# cos_POC.net
KiCad netlist of a schematic drawn in EAGLE
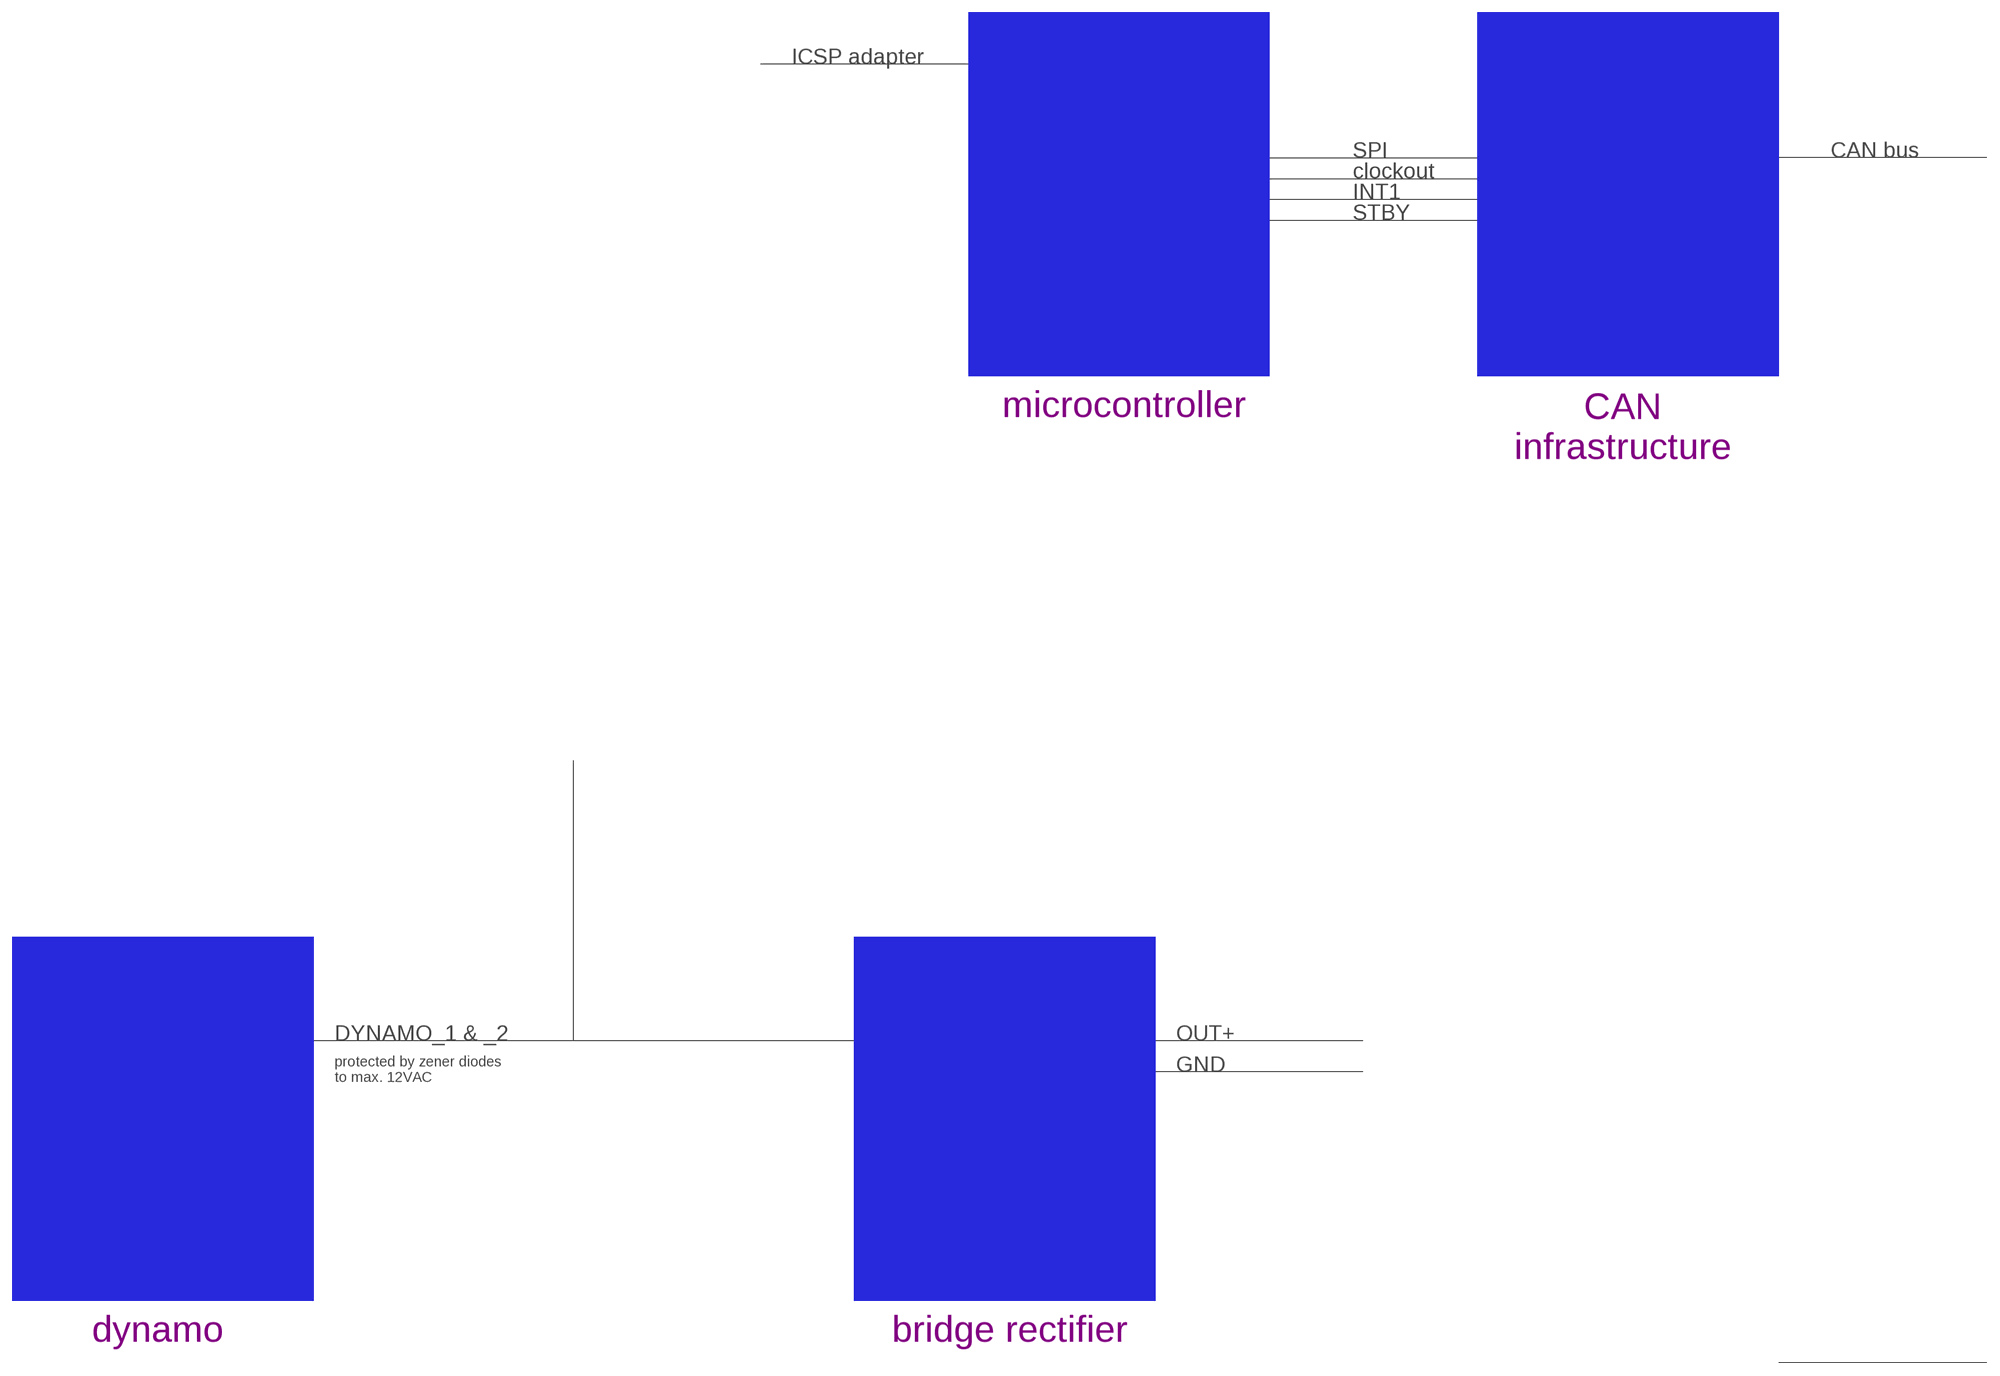
[diagram p0: schematic, sheet 1, part 1 of 3]
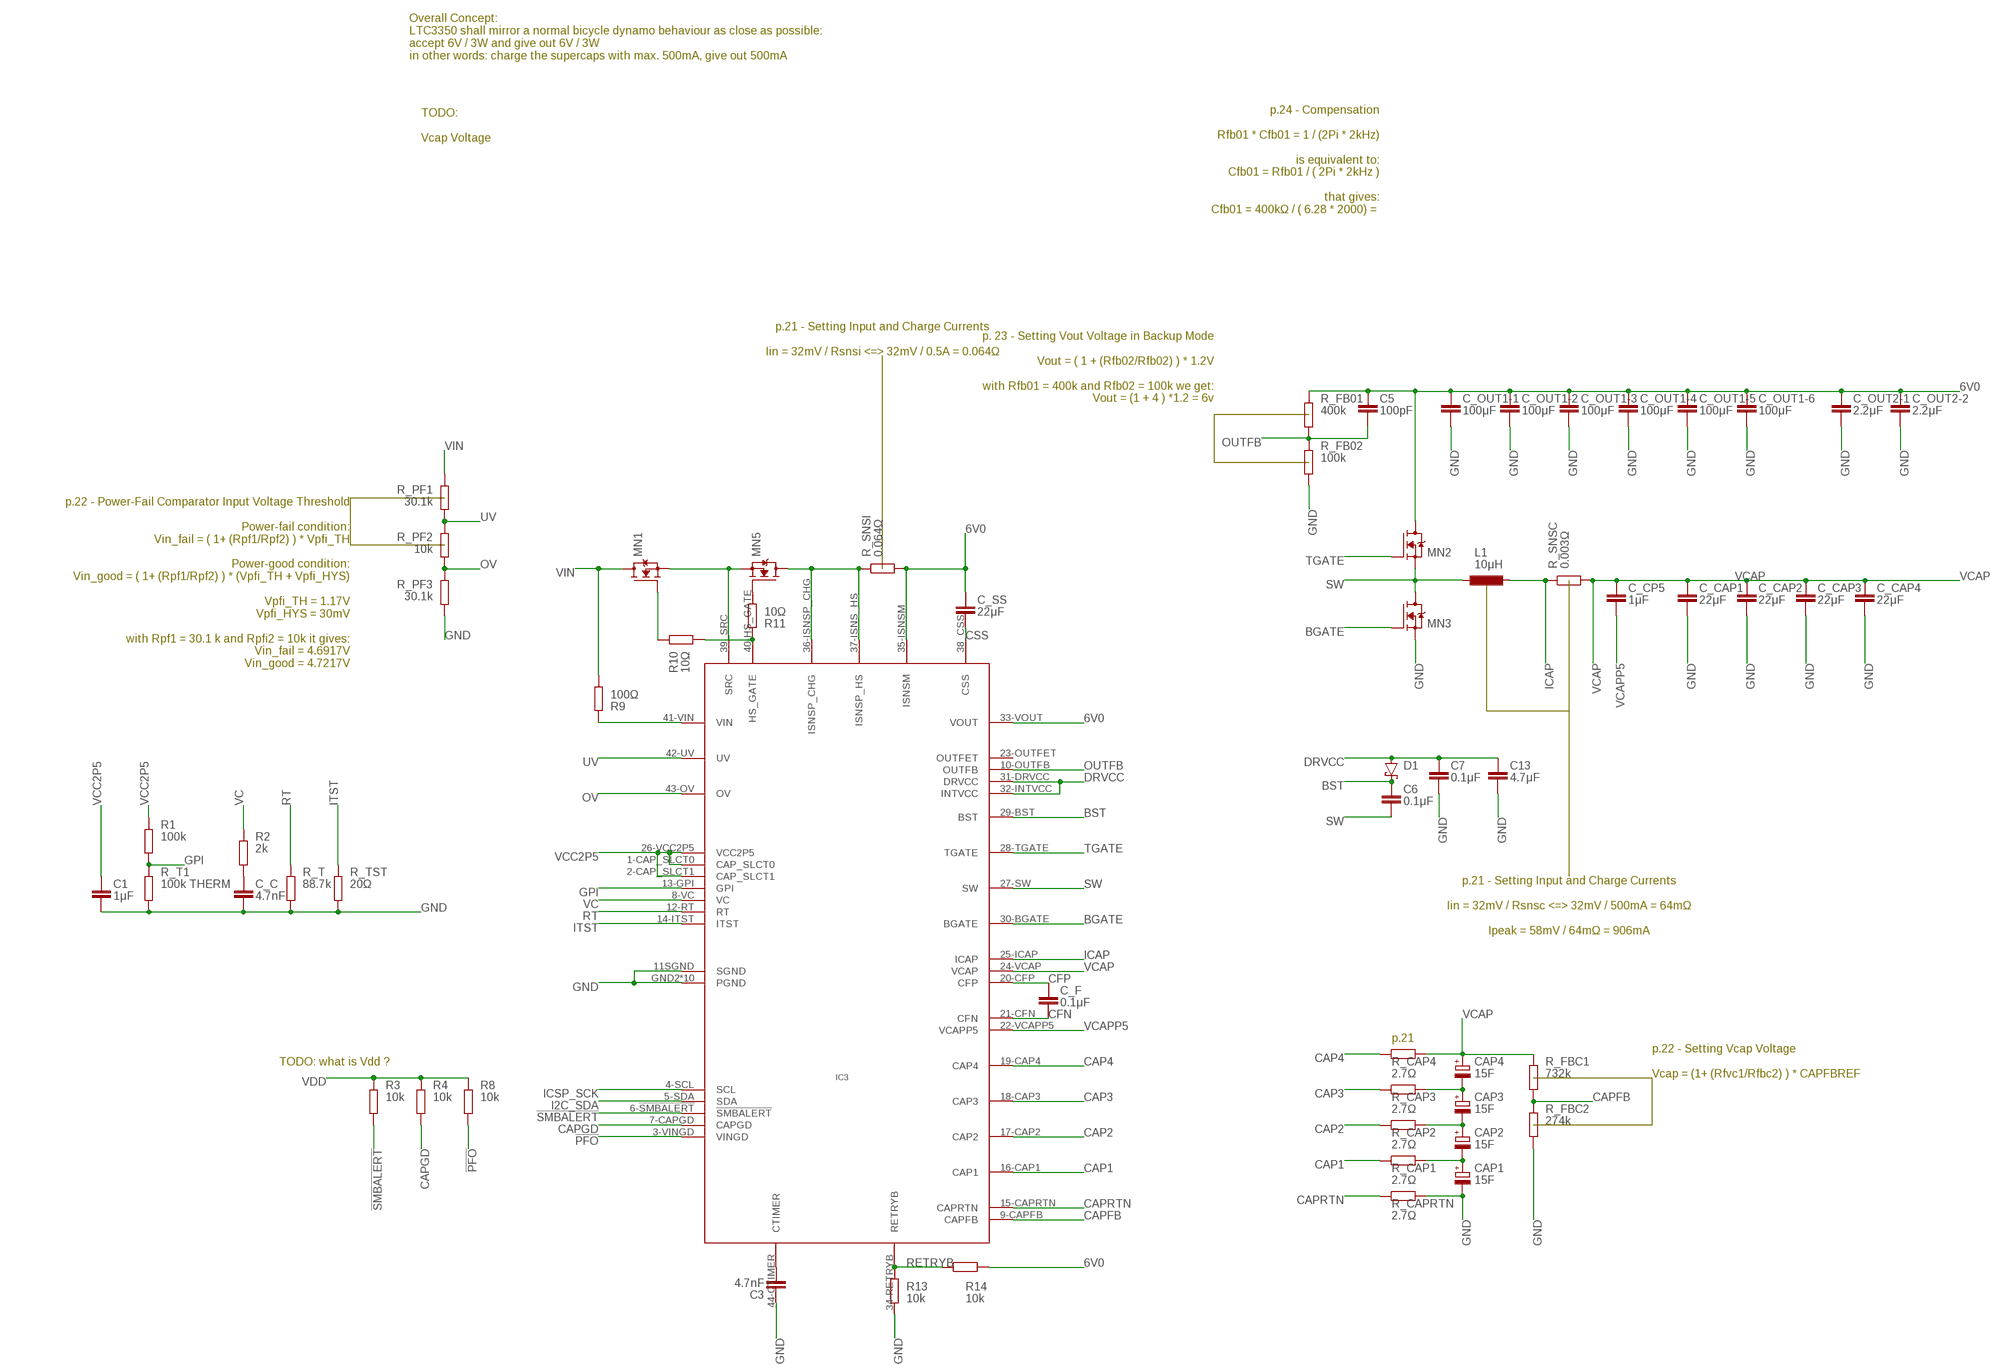
[diagram p1: schematic, sheet 1, part 2 of 3]
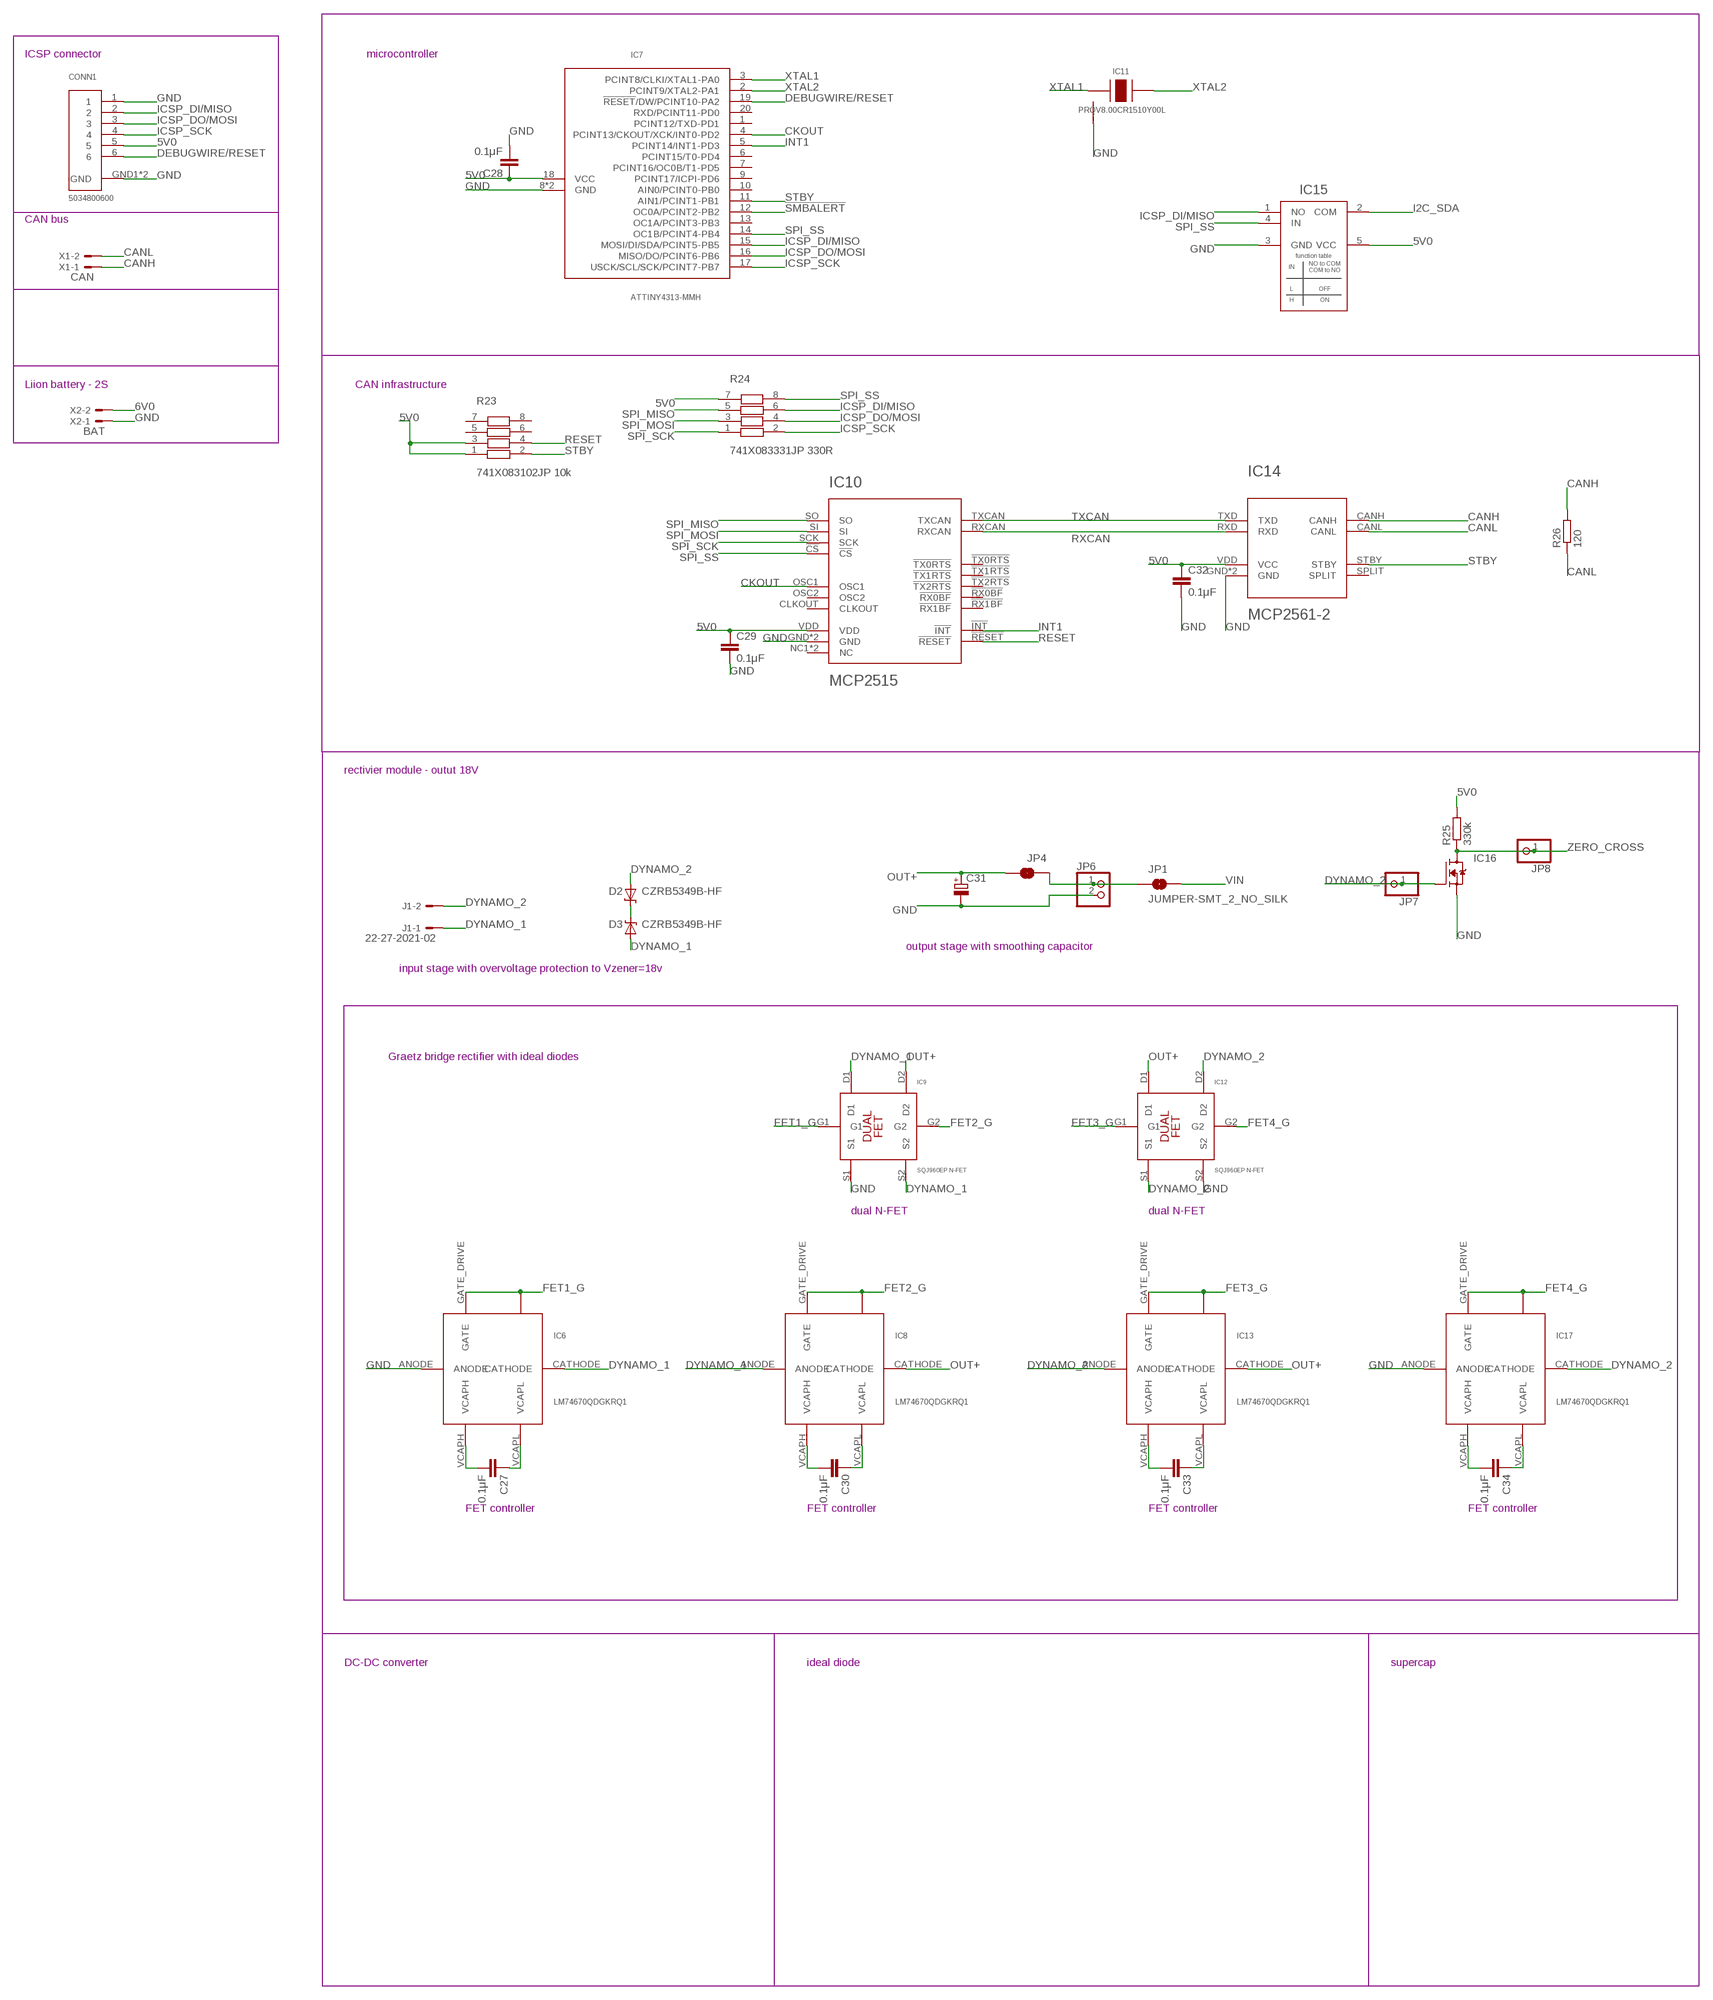
[diagram p2: schematic, sheet 1, part 3 of 3]

(export (version "E")
  (design (tool "Eeschema 10.0.6"))
  (components
    (comp (ref "C1")
      (value "1μF")
      (footprint "eagle-import:C0402")
      (libsource (lib "eagle-import") (part "C-EUC0402"))
    )
    (comp (ref "C3")
      (value "4.7nF")
      (footprint "eagle-import:C0402")
      (libsource (lib "eagle-import") (part "C-EUC0402"))
    )
    (comp (ref "C5")
      (value "100pF")
      (footprint "eagle-import:C0402")
      (libsource (lib "eagle-import") (part "C-EUC0402"))
    )
    (comp (ref "C6")
      (value "0.1μF")
      (footprint "eagle-import:C0402")
      (libsource (lib "eagle-import") (part "C-EUC0402"))
    )
    (comp (ref "C7")
      (value "0.1μF")
      (footprint "eagle-import:C0402")
      (libsource (lib "eagle-import") (part "C-EUC0402"))
    )
    (comp (ref "C13")
      (value "4.7μF")
      (footprint "eagle-import:C0402")
      (libsource (lib "eagle-import") (part "C-EUC0402"))
    )
    (comp (ref "C27")
      (value "0.1μF")
      (footprint "eagle-import:C0805")
      (libsource (lib "eagle-import") (part "C-EUC0805"))
    )
    (comp (ref "C28")
      (value "0.1μF")
      (footprint "eagle-import:C0402")
      (libsource (lib "eagle-import") (part "C-EUC0402"))
    )
    (comp (ref "C29")
      (value "0.1μF")
      (footprint "eagle-import:C0402")
      (libsource (lib "eagle-import") (part "C-EUC0402"))
    )
    (comp (ref "C30")
      (value "0.1μF")
      (footprint "eagle-import:C0805")
      (libsource (lib "eagle-import") (part "C-EUC0805"))
    )
    (comp (ref "C31")
      (value "CPOL-EUB45181A")
      (footprint "eagle-import:B45181A")
      (libsource (lib "eagle-import") (part "CPOL-EUB45181A"))
    )
    (comp (ref "C32")
      (value "0.1μF")
      (footprint "eagle-import:C0402")
      (libsource (lib "eagle-import") (part "C-EUC0402"))
    )
    (comp (ref "C33")
      (value "0.1μF")
      (footprint "eagle-import:C0805")
      (libsource (lib "eagle-import") (part "C-EUC0805"))
    )
    (comp (ref "C34")
      (value "0.1μF")
      (footprint "eagle-import:C0805")
      (libsource (lib "eagle-import") (part "C-EUC0805"))
    )
    (comp (ref "CAP1")
      (value "15F")
      (footprint "eagle-import:E5-8,5")
      (libsource (lib "eagle-import") (part "CPOL-EUE5-8.5"))
    )
    (comp (ref "CAP2")
      (value "15F")
      (footprint "eagle-import:E5-8,5")
      (libsource (lib "eagle-import") (part "CPOL-EUE5-8.5"))
    )
    (comp (ref "CAP3")
      (value "15F")
      (footprint "eagle-import:E5-8,5")
      (libsource (lib "eagle-import") (part "CPOL-EUE5-8.5"))
    )
    (comp (ref "CAP4")
      (value "15F")
      (footprint "eagle-import:E5-8,5")
      (libsource (lib "eagle-import") (part "CPOL-EUE5-8.5"))
    )
    (comp (ref "CONN1")
      (value "5034800600")
      (footprint "eagle-import:SMT")
      (libsource (lib "eagle-import") (part "5034800600"))
    )
    (comp (ref "C_C")
      (value "4.7nF")
      (footprint "eagle-import:C0402")
      (libsource (lib "eagle-import") (part "C-EUC0402"))
    )
    (comp (ref "C_CAP1")
      (value "22μF")
      (footprint "eagle-import:C0402")
      (libsource (lib "eagle-import") (part "C-EUC0402"))
    )
    (comp (ref "C_CAP2")
      (value "22μF")
      (footprint "eagle-import:C0402")
      (libsource (lib "eagle-import") (part "C-EUC0402"))
    )
    (comp (ref "C_CAP3")
      (value "22μF")
      (footprint "eagle-import:C0402")
      (libsource (lib "eagle-import") (part "C-EUC0402"))
    )
    (comp (ref "C_CAP4")
      (value "22μF")
      (footprint "eagle-import:C0402")
      (libsource (lib "eagle-import") (part "C-EUC0402"))
    )
    (comp (ref "C_CP5")
      (value "1μF")
      (footprint "eagle-import:C0402")
      (libsource (lib "eagle-import") (part "C-EUC0402"))
    )
    (comp (ref "C_F")
      (value "0.1μF")
      (footprint "eagle-import:C0402")
      (libsource (lib "eagle-import") (part "C-EUC0402"))
    )
    (comp (ref "C_OUT1-1")
      (value "100μF")
      (footprint "eagle-import:C0402")
      (libsource (lib "eagle-import") (part "C-EUC0402"))
    )
    (comp (ref "C_OUT1-2")
      (value "100μF")
      (footprint "eagle-import:C0402")
      (libsource (lib "eagle-import") (part "C-EUC0402"))
    )
    (comp (ref "C_OUT1-3")
      (value "100μF")
      (footprint "eagle-import:C0402")
      (libsource (lib "eagle-import") (part "C-EUC0402"))
    )
    (comp (ref "C_OUT1-4")
      (value "100μF")
      (footprint "eagle-import:C0402")
      (libsource (lib "eagle-import") (part "C-EUC0402"))
    )
    (comp (ref "C_OUT1-5")
      (value "100μF")
      (footprint "eagle-import:C0402")
      (libsource (lib "eagle-import") (part "C-EUC0402"))
    )
    (comp (ref "C_OUT1-6")
      (value "100μF")
      (footprint "eagle-import:C0402")
      (libsource (lib "eagle-import") (part "C-EUC0402"))
    )
    (comp (ref "C_OUT2-1")
      (value "2.2μF")
      (footprint "eagle-import:C0402")
      (libsource (lib "eagle-import") (part "C-EUC0402"))
    )
    (comp (ref "C_OUT2-2")
      (value "2.2μF")
      (footprint "eagle-import:C0402")
      (libsource (lib "eagle-import") (part "C-EUC0402"))
    )
    (comp (ref "C_SS")
      (value "22μF")
      (footprint "eagle-import:C0402")
      (libsource (lib "eagle-import") (part "C-EUC0402"))
    )
    (comp (ref "D1")
      (value "SCHOTTKY-DIODESMC")
      (footprint "eagle-import:SMC")
      (libsource (lib "eagle-import") (part "SCHOTTKY-DIODESMC"))
    )
    (comp (ref "D2")
      (value "CZRB5349B-HF")
      (footprint "eagle-import:DO-214")
      (libsource (lib "eagle-import") (part "ZENER"))
    )
    (comp (ref "D3")
      (value "CZRB5349B-HF")
      (footprint "eagle-import:DO-214")
      (libsource (lib "eagle-import") (part "ZENER"))
    )
    (comp (ref "IC3")
      (value "LTC3351")
      (footprint "eagle-import:QFN44")
      (libsource (lib "eagle-import") (part "LTC3351"))
    )
    (comp (ref "IC6")
      (value "LM74670QDGKRQ1")
      (footprint "eagle-import:VSSOP-8")
      (libsource (lib "eagle-import") (part "LM74670"))
    )
    (comp (ref "IC7")
      (value "ATTINY4313-MMH")
      (footprint "eagle-import:VQFN-20")
      (libsource (lib "eagle-import") (part "ATTINY4313VQFN-20"))
    )
    (comp (ref "IC8")
      (value "LM74670QDGKRQ1")
      (footprint "eagle-import:VSSOP-8")
      (libsource (lib "eagle-import") (part "LM74670"))
    )
    (comp (ref "IC9")
      (value "SQJ960EP N-FET")
      (footprint "eagle-import:SO-8L")
      (libsource (lib "eagle-import") (part "SQJ96XEP"))
    )
    (comp (ref "IC10")
      (value "MCP2515")
      (footprint "eagle-import:QFN20")
      (libsource (lib "eagle-import") (part "MCP2515-I-ML"))
    )
    (comp (ref "IC11")
      (value "PRQV8.00CR1510Y00L")
      (footprint "eagle-import:SMT")
      (libsource (lib "eagle-import") (part "PRQV"))
    )
    (comp (ref "IC12")
      (value "SQJ960EP N-FET")
      (footprint "eagle-import:SO-8L")
      (libsource (lib "eagle-import") (part "SQJ96XEP"))
    )
    (comp (ref "IC13")
      (value "LM74670QDGKRQ1")
      (footprint "eagle-import:VSSOP-8")
      (libsource (lib "eagle-import") (part "LM74670"))
    )
    (comp (ref "IC14")
      (value "MCP2561-2")
      (footprint "eagle-import:DFN10")
      (libsource (lib "eagle-import") (part "MCP2561-2"))
    )
    (comp (ref "IC15")
      (value "TS5A1066SOT-23")
      (footprint "eagle-import:SOT-23")
      (libsource (lib "eagle-import") (part "TS5A1066SOT-23"))
    )
    (comp (ref "IC16")
      (value "SIA456DJ")
      (footprint "eagle-import:SC-70-6")
      (libsource (lib "eagle-import") (part "SIA456DJ"))
    )
    (comp (ref "IC17")
      (value "LM74670QDGKRQ1")
      (footprint "eagle-import:VSSOP-8")
      (libsource (lib "eagle-import") (part "LM74670"))
    )
    (comp (ref "J1")
      (value "22-27-2021-02")
      (footprint "eagle-import:6410-02")
      (fields (field (name "MF") "MOLEX"))
      (libsource (lib "eagle-import") (part "22-?-0227-2021"))
    )
    (comp (ref "JP1")
      (value "JUMPER-SMT_2_NO_SILK")
      (footprint "eagle-import:SMT-JUMPER_2_NO_SILK")
      (libsource (lib "eagle-import") (part "JUMPER-SMT_2_NO_SILK"))
    )
    (comp (ref "JP4")
      (value "JUMPER-SMT_2_NO_SILK")
      (footprint "eagle-import:SMT-JUMPER_2_NO_SILK")
      (libsource (lib "eagle-import") (part "JUMPER-SMT_2_NO_SILK"))
    )
    (comp (ref "JP6")
      (value "PINHD-1X2")
      (footprint "eagle-import:1X02")
      (libsource (lib "eagle-import") (part "PINHD-1X2"))
    )
    (comp (ref "JP7")
      (value "PINHD-1X1")
      (footprint "eagle-import:1X01")
      (libsource (lib "eagle-import") (part "PINHD-1X1"))
    )
    (comp (ref "JP8")
      (value "PINHD-1X1")
      (footprint "eagle-import:1X01")
      (libsource (lib "eagle-import") (part "PINHD-1X1"))
    )
    (comp (ref "L1")
      (value "10μH")
      (footprint "eagle-import:L1812")
      (libsource (lib "eagle-import") (part "L-EUL1812"))
    )
    (comp (ref "MN1")
      (value "SIA456DJ")
      (footprint "eagle-import:SC-70-6")
      (libsource (lib "eagle-import") (part "SIA456DJ"))
    )
    (comp (ref "MN2")
      (value "SIA456DJ")
      (footprint "eagle-import:SC-70-6")
      (libsource (lib "eagle-import") (part "SIA456DJ"))
    )
    (comp (ref "MN3")
      (value "SIA456DJ")
      (footprint "eagle-import:SC-70-6")
      (libsource (lib "eagle-import") (part "SIA456DJ"))
    )
    (comp (ref "MN5")
      (value "SIA456DJ")
      (footprint "eagle-import:SC-70-6")
      (libsource (lib "eagle-import") (part "SIA456DJ"))
    )
    (comp (ref "R1")
      (value "100k")
      (footprint "eagle-import:R0402")
      (libsource (lib "eagle-import") (part "R-EU_R0402"))
    )
    (comp (ref "R2")
      (value "2k")
      (footprint "eagle-import:R0402")
      (libsource (lib "eagle-import") (part "R-EU_R0402"))
    )
    (comp (ref "R3")
      (value "10k")
      (footprint "eagle-import:R0402")
      (libsource (lib "eagle-import") (part "R-EU_R0402"))
    )
    (comp (ref "R4")
      (value "10k")
      (footprint "eagle-import:R0402")
      (libsource (lib "eagle-import") (part "R-EU_R0402"))
    )
    (comp (ref "R8")
      (value "10k")
      (footprint "eagle-import:R0402")
      (libsource (lib "eagle-import") (part "R-EU_R0402"))
    )
    (comp (ref "R9")
      (value "100Ω")
      (footprint "eagle-import:R0402")
      (libsource (lib "eagle-import") (part "R-EU_R0402"))
    )
    (comp (ref "R10")
      (value "10Ω")
      (footprint "eagle-import:R0402")
      (libsource (lib "eagle-import") (part "R-EU_R0402"))
    )
    (comp (ref "R11")
      (value "10Ω")
      (footprint "eagle-import:R0402")
      (libsource (lib "eagle-import") (part "R-EU_R0402"))
    )
    (comp (ref "R13")
      (value "10k")
      (footprint "eagle-import:R0402")
      (libsource (lib "eagle-import") (part "R-EU_R0402"))
    )
    (comp (ref "R14")
      (value "10k")
      (footprint "eagle-import:R0402")
      (libsource (lib "eagle-import") (part "R-EU_R0402"))
    )
    (comp (ref "R23")
      (value "741X083102JP 10k")
      (footprint "eagle-import:0402-4R")
      (libsource (lib "eagle-import") (part "741X083331JP"))
    )
    (comp (ref "R24")
      (value "741X083331JP 330R")
      (footprint "eagle-import:0402-4R")
      (libsource (lib "eagle-import") (part "741X083331JP"))
    )
    (comp (ref "R25")
      (value "330k")
      (footprint "eagle-import:R0805")
      (libsource (lib "eagle-import") (part "R-EU_R0805"))
    )
    (comp (ref "R26")
      (value "120")
      (footprint "eagle-import:R0805")
      (libsource (lib "eagle-import") (part "R-EU_R0805"))
    )
    (comp (ref "R_CAP1")
      (value "2.7Ω")
      (footprint "eagle-import:R0402")
      (libsource (lib "eagle-import") (part "R-EU_R0402"))
    )
    (comp (ref "R_CAP2")
      (value "2.7Ω")
      (footprint "eagle-import:R0402")
      (libsource (lib "eagle-import") (part "R-EU_R0402"))
    )
    (comp (ref "R_CAP3")
      (value "2.7Ω")
      (footprint "eagle-import:R0402")
      (libsource (lib "eagle-import") (part "R-EU_R0402"))
    )
    (comp (ref "R_CAP4")
      (value "2.7Ω")
      (footprint "eagle-import:R0402")
      (libsource (lib "eagle-import") (part "R-EU_R0402"))
    )
    (comp (ref "R_CAPRTN")
      (value "2.7Ω")
      (footprint "eagle-import:R0402")
      (libsource (lib "eagle-import") (part "R-EU_R0402"))
    )
    (comp (ref "R_FB01")
      (value "400k")
      (footprint "eagle-import:R0402")
      (libsource (lib "eagle-import") (part "R-EU_R0402"))
    )
    (comp (ref "R_FB02")
      (value "100k")
      (footprint "eagle-import:R0402")
      (libsource (lib "eagle-import") (part "R-EU_R0402"))
    )
    (comp (ref "R_FBC1")
      (value "732k")
      (footprint "eagle-import:R0402")
      (libsource (lib "eagle-import") (part "R-EU_R0402"))
    )
    (comp (ref "R_FBC2")
      (value "274k")
      (footprint "eagle-import:R0402")
      (libsource (lib "eagle-import") (part "R-EU_R0402"))
    )
    (comp (ref "R_PF1")
      (value "30.1k")
      (footprint "eagle-import:R0402")
      (libsource (lib "eagle-import") (part "R-EU_R0402"))
    )
    (comp (ref "R_PF2")
      (value "10k")
      (footprint "eagle-import:R0402")
      (libsource (lib "eagle-import") (part "R-EU_R0402"))
    )
    (comp (ref "R_PF3")
      (value "30.1k")
      (footprint "eagle-import:R0402")
      (libsource (lib "eagle-import") (part "R-EU_R0402"))
    )
    (comp (ref "R_SNSC")
      (value "0.003Ω")
      (footprint "eagle-import:R0402")
      (libsource (lib "eagle-import") (part "R-EU_R0402"))
    )
    (comp (ref "R_SNSI")
      (value "0.064Ω")
      (footprint "eagle-import:R0402")
      (libsource (lib "eagle-import") (part "R-EU_R0402"))
    )
    (comp (ref "R_T")
      (value "88.7k")
      (footprint "eagle-import:R0402")
      (libsource (lib "eagle-import") (part "R-EU_R0402"))
    )
    (comp (ref "R_T1")
      (value "100k THERM")
      (footprint "eagle-import:R0402")
      (libsource (lib "eagle-import") (part "R-EU_R0402"))
    )
    (comp (ref "R_TST")
      (value "20Ω")
      (footprint "eagle-import:R0402")
      (libsource (lib "eagle-import") (part "R-EU_R0402"))
    )
    (comp (ref "X1")
      (value "CAN")
      (footprint "eagle-import:22-23-2021")
      (fields (field (name "MF") "MOLEX") (field (name "MPN") "22-23-2021"))
      (libsource (lib "eagle-import") (part "22-23-2021"))
    )
    (comp (ref "X2")
      (value "BAT")
      (footprint "eagle-import:22-23-2021")
      (fields (field (name "MF") "MOLEX") (field (name "MPN") "22-23-2021"))
      (libsource (lib "eagle-import") (part "22-23-2021"))
    )
  )
  (nets
    (net (code "1") (name "/5V0") (class "Default")
      (node (ref "C28") (pin "1") (pinfunction "1_1") (pintype "passive"))
      (node (ref "C29") (pin "1") (pinfunction "1_1") (pintype "passive"))
      (node (ref "C32") (pin "1") (pinfunction "1_1") (pintype "passive"))
      (node (ref "CONN1") (pin "5") (pinfunction "5_5") (pintype "bidirectional"))
      (node (ref "IC10") (pin "VDD") (pinfunction "VDD_VDD") (pintype "power_in"))
      (node (ref "IC14") (pin "VDD") (pinfunction "VCC_VDD") (pintype "power_in"))
      (node (ref "IC15") (pin "5") (pinfunction "VCC_5") (pintype "bidirectional"))
      (node (ref "IC7") (pin "18") (pinfunction "VCC_18") (pintype "bidirectional"))
      (node (ref "R23") (pin "1") (pinfunction "1_1") (pintype "bidirectional"))
      (node (ref "R23") (pin "3") (pinfunction "3_3") (pintype "bidirectional"))
      (node (ref "R24") (pin "7") (pinfunction "7_7") (pintype "bidirectional"))
      (node (ref "R25") (pin "2") (pinfunction "2_2") (pintype "passive"))
    )
    (net (code "2") (name "/6V0") (class "Default")
      (node (ref "C5") (pin "1") (pinfunction "1_1") (pintype "passive"))
      (node (ref "C_OUT1-1") (pin "1") (pinfunction "1_1") (pintype "passive"))
      (node (ref "C_OUT1-2") (pin "1") (pinfunction "1_1") (pintype "passive"))
      (node (ref "C_OUT1-3") (pin "1") (pinfunction "1_1") (pintype "passive"))
      (node (ref "C_OUT1-4") (pin "1") (pinfunction "1_1") (pintype "passive"))
      (node (ref "C_OUT1-5") (pin "1") (pinfunction "1_1") (pintype "passive"))
      (node (ref "C_OUT1-6") (pin "1") (pinfunction "1_1") (pintype "passive"))
      (node (ref "C_OUT2-1") (pin "1") (pinfunction "1_1") (pintype "passive"))
      (node (ref "C_OUT2-2") (pin "1") (pinfunction "1_1") (pintype "passive"))
      (node (ref "C_SS") (pin "1") (pinfunction "1_1") (pintype "passive"))
      (node (ref "IC3") (pin "33-VOUT") (pinfunction "VOUT_33-VOUT") (pintype "bidirectional"))
      (node (ref "IC3") (pin "35-ISNSM") (pinfunction "ISNSM_35-ISNSM") (pintype "bidirectional"))
      (node (ref "MN2") (pin "1D") (pinfunction "D_1D") (pintype "passive"))
      (node (ref "MN2") (pin "2D") (pinfunction "D_2D") (pintype "passive"))
      (node (ref "MN2") (pin "5D") (pinfunction "D_5D") (pintype "passive"))
      (node (ref "MN2") (pin "6D") (pinfunction "D_6D") (pintype "passive"))
      (node (ref "MN2") (pin "D") (pinfunction "D_D") (pintype "passive"))
      (node (ref "R14") (pin "2") (pinfunction "2_2") (pintype "passive"))
      (node (ref "R_FB01") (pin "1") (pinfunction "1_1") (pintype "passive"))
      (node (ref "R_SNSI") (pin "2") (pinfunction "2_2") (pintype "passive"))
      (node (ref "X2") (pin "2") (pinfunction "S_2") (pintype "passive"))
    )
    (net (code "3") (name "/BGATE") (class "Default")
      (node (ref "IC3") (pin "30-BGATE") (pinfunction "BGATE_30-BGATE") (pintype "bidirectional"))
      (node (ref "MN3") (pin "3G") (pinfunction "G_3G") (pintype "passive"))
    )
    (net (code "4") (name "/BST") (class "Default")
      (node (ref "C6") (pin "1") (pinfunction "1_1") (pintype "passive"))
      (node (ref "D1") (pin "C") (pinfunction "C_C") (pintype "passive"))
      (node (ref "IC3") (pin "29-BST") (pinfunction "BST_29-BST") (pintype "bidirectional"))
    )
    (net (code "5") (name "/CANH") (class "Default")
      (node (ref "IC14") (pin "CANH") (pinfunction "CANH_CANH") (pintype "bidirectional"))
      (node (ref "R26") (pin "2") (pinfunction "2_2") (pintype "passive"))
      (node (ref "X1") (pin "1") (pinfunction "S_1") (pintype "passive"))
    )
    (net (code "6") (name "/CANL") (class "Default")
      (node (ref "IC14") (pin "CANL") (pinfunction "CANL_CANL") (pintype "bidirectional"))
      (node (ref "R26") (pin "1") (pinfunction "1_1") (pintype "passive"))
      (node (ref "X1") (pin "2") (pinfunction "S_2") (pintype "passive"))
    )
    (net (code "7") (name "/CAP1") (class "Default")
      (node (ref "IC3") (pin "16-CAP1") (pinfunction "CAP1_16-CAP1") (pintype "bidirectional"))
      (node (ref "R_CAP1") (pin "1") (pinfunction "1_1") (pintype "passive"))
    )
    (net (code "8") (name "/CAP2") (class "Default")
      (node (ref "IC3") (pin "17-CAP2") (pinfunction "CAP2_17-CAP2") (pintype "bidirectional"))
      (node (ref "R_CAP2") (pin "1") (pinfunction "1_1") (pintype "passive"))
    )
    (net (code "9") (name "/CAP3") (class "Default")
      (node (ref "IC3") (pin "18-CAP3") (pinfunction "CAP3_18-CAP3") (pintype "bidirectional"))
      (node (ref "R_CAP3") (pin "1") (pinfunction "1_1") (pintype "passive"))
    )
    (net (code "10") (name "/CAP4") (class "Default")
      (node (ref "IC3") (pin "19-CAP4") (pinfunction "CAP4_19-CAP4") (pintype "bidirectional"))
      (node (ref "R_CAP4") (pin "1") (pinfunction "1_1") (pintype "passive"))
    )
    (net (code "11") (name "/CAPFB") (class "Default")
      (node (ref "IC3") (pin "9-CAPFB") (pinfunction "CAPFB_9-CAPFB") (pintype "bidirectional"))
      (node (ref "R_FBC1") (pin "1") (pinfunction "1_1") (pintype "passive"))
      (node (ref "R_FBC2") (pin "2") (pinfunction "2_2") (pintype "passive"))
    )
    (net (code "12") (name "/CAPGD") (class "Default")
      (node (ref "IC3") (pin "7-CAPGD") (pinfunction "CAPGD_7-CAPGD") (pintype "output"))
      (node (ref "R4") (pin "2") (pinfunction "2_2") (pintype "passive"))
    )
    (net (code "13") (name "/CAPRTN") (class "Default")
      (node (ref "IC3") (pin "15-CAPRTN") (pinfunction "CAPRTN_15-CAPRTN") (pintype "bidirectional"))
      (node (ref "R_CAPRTN") (pin "1") (pinfunction "1_1") (pintype "passive"))
    )
    (net (code "14") (name "/CFN") (class "Default")
      (node (ref "C_F") (pin "2") (pinfunction "2_2") (pintype "passive"))
      (node (ref "IC3") (pin "21-CFN") (pinfunction "CFN_21-CFN") (pintype "bidirectional"))
    )
    (net (code "15") (name "/CFP") (class "Default")
      (node (ref "C_F") (pin "1") (pinfunction "1_1") (pintype "passive"))
      (node (ref "IC3") (pin "20-CFP") (pinfunction "CFP_20-CFP") (pintype "bidirectional"))
    )
    (net (code "16") (name "/CKOUT") (class "Default")
      (node (ref "IC10") (pin "OSC1") (pinfunction "OSC1_OSC1") (pintype "bidirectional"))
      (node (ref "IC7") (pin "4") (pinfunction "PCINT13/CKOUT/XCK/INT0-PD2_4") (pintype "bidirectional"))
    )
    (net (code "17") (name "/CSS") (class "Default")
      (node (ref "C_SS") (pin "2") (pinfunction "2_2") (pintype "passive"))
      (node (ref "IC3") (pin "38_CSS") (pinfunction "CSS_38_CSS") (pintype "bidirectional"))
    )
    (net (code "18") (name "/DEBUGWIRE{slash}RESET") (class "Default")
      (node (ref "CONN1") (pin "6") (pinfunction "6_6") (pintype "bidirectional"))
      (node (ref "IC7") (pin "19") (pinfunction "~{RESET}/DW/PCINT10-PA2_19") (pintype "bidirectional"))
    )
    (net (code "19") (name "/DRVCC") (class "Default")
      (node (ref "C13") (pin "1") (pinfunction "1_1") (pintype "passive"))
      (node (ref "C7") (pin "1") (pinfunction "1_1") (pintype "passive"))
      (node (ref "D1") (pin "A") (pinfunction "A_A") (pintype "passive"))
      (node (ref "IC3") (pin "31-DRVCC") (pinfunction "DRVCC_31-DRVCC") (pintype "bidirectional"))
      (node (ref "IC3") (pin "32-INTVCC") (pinfunction "INTVCC_32-INTVCC") (pintype "bidirectional"))
    )
    (net (code "20") (name "/DYNAMO_1") (class "Default")
      (node (ref "D3") (pin "AN") (pinfunction "AN_AN") (pintype "passive"))
      (node (ref "IC6") (pin "CATHODE") (pinfunction "CATHODE_CATHODE") (pintype "bidirectional"))
      (node (ref "IC8") (pin "ANODE") (pinfunction "ANODE_ANODE") (pintype "bidirectional"))
      (node (ref "IC9") (pin "D1") (pinfunction "D1_D1") (pintype "bidirectional"))
      (node (ref "IC9") (pin "S2") (pinfunction "S2_S2") (pintype "bidirectional"))
      (node (ref "J1") (pin "1") (pinfunction "S_1") (pintype "passive"))
    )
    (net (code "21") (name "/DYNAMO_2") (class "Default")
      (node (ref "D2") (pin "AN") (pinfunction "AN_AN") (pintype "passive"))
      (node (ref "IC12") (pin "D2") (pinfunction "D2_D2") (pintype "bidirectional"))
      (node (ref "IC12") (pin "S1") (pinfunction "S1_S1") (pintype "bidirectional"))
      (node (ref "IC13") (pin "ANODE") (pinfunction "ANODE_ANODE") (pintype "bidirectional"))
      (node (ref "IC16") (pin "3G") (pinfunction "G_3G") (pintype "passive"))
      (node (ref "IC17") (pin "CATHODE") (pinfunction "CATHODE_CATHODE") (pintype "bidirectional"))
      (node (ref "J1") (pin "2") (pinfunction "S_2") (pintype "passive"))
      (node (ref "JP7") (pin "1") (pinfunction "1_1") (pintype "passive"))
    )
    (net (code "22") (name "/FET1_G") (class "Default")
      (node (ref "IC6") (pin "GATE_DRIVE") (pinfunction "GATE_GATE_DRIVE") (pintype "bidirectional"))
      (node (ref "IC6") (pin "GATE_PULLD") (pinfunction "GATE_PULLD_GATE_PULLD") (pintype "bidirectional"))
      (node (ref "IC9") (pin "G1") (pinfunction "G1_G1") (pintype "bidirectional"))
    )
    (net (code "23") (name "/FET2_G") (class "Default")
      (node (ref "IC8") (pin "GATE_DRIVE") (pinfunction "GATE_GATE_DRIVE") (pintype "bidirectional"))
      (node (ref "IC8") (pin "GATE_PULLD") (pinfunction "GATE_PULLD_GATE_PULLD") (pintype "bidirectional"))
      (node (ref "IC9") (pin "G2") (pinfunction "G2_G2") (pintype "bidirectional"))
    )
    (net (code "24") (name "/FET3_G") (class "Default")
      (node (ref "IC12") (pin "G1") (pinfunction "G1_G1") (pintype "bidirectional"))
      (node (ref "IC13") (pin "GATE_DRIVE") (pinfunction "GATE_GATE_DRIVE") (pintype "bidirectional"))
      (node (ref "IC13") (pin "GATE_PULLD") (pinfunction "GATE_PULLD_GATE_PULLD") (pintype "bidirectional"))
    )
    (net (code "25") (name "/FET4_G") (class "Default")
      (node (ref "IC12") (pin "G2") (pinfunction "G2_G2") (pintype "bidirectional"))
      (node (ref "IC17") (pin "GATE_DRIVE") (pinfunction "GATE_GATE_DRIVE") (pintype "bidirectional"))
      (node (ref "IC17") (pin "GATE_PULLD") (pinfunction "GATE_PULLD_GATE_PULLD") (pintype "bidirectional"))
    )
    (net (code "26") (name "/GND") (class "Default")
      (node (ref "C1") (pin "2") (pinfunction "2_2") (pintype "passive"))
      (node (ref "C13") (pin "2") (pinfunction "2_2") (pintype "passive"))
      (node (ref "C28") (pin "2") (pinfunction "2_2") (pintype "passive"))
      (node (ref "C29") (pin "2") (pinfunction "2_2") (pintype "passive"))
      (node (ref "C3") (pin "1") (pinfunction "1_1") (pintype "passive"))
      (node (ref "C31") (pin "-") (pinfunction "-_-") (pintype "passive"))
      (node (ref "C32") (pin "2") (pinfunction "2_2") (pintype "passive"))
      (node (ref "C7") (pin "2") (pinfunction "2_2") (pintype "passive"))
      (node (ref "CAP1") (pin "-") (pinfunction "-_-") (pintype "passive"))
      (node (ref "CONN1") (pin "1") (pinfunction "1_1") (pintype "bidirectional"))
      (node (ref "CONN1") (pin "GND1") (pinfunction "GND_GND1") (pintype "bidirectional"))
      (node (ref "CONN1") (pin "GND2") (pinfunction "GND_GND2") (pintype "bidirectional"))
      (node (ref "C_C") (pin "2") (pinfunction "2_2") (pintype "passive"))
      (node (ref "C_CAP1") (pin "2") (pinfunction "2_2") (pintype "passive"))
      (node (ref "C_CAP2") (pin "2") (pinfunction "2_2") (pintype "passive"))
      (node (ref "C_CAP3") (pin "2") (pinfunction "2_2") (pintype "passive"))
      (node (ref "C_CAP4") (pin "2") (pinfunction "2_2") (pintype "passive"))
      (node (ref "C_OUT1-1") (pin "2") (pinfunction "2_2") (pintype "passive"))
      (node (ref "C_OUT1-2") (pin "2") (pinfunction "2_2") (pintype "passive"))
      (node (ref "C_OUT1-3") (pin "2") (pinfunction "2_2") (pintype "passive"))
      (node (ref "C_OUT1-4") (pin "2") (pinfunction "2_2") (pintype "passive"))
      (node (ref "C_OUT1-5") (pin "2") (pinfunction "2_2") (pintype "passive"))
      (node (ref "C_OUT1-6") (pin "2") (pinfunction "2_2") (pintype "passive"))
      (node (ref "C_OUT2-1") (pin "2") (pinfunction "2_2") (pintype "passive"))
      (node (ref "C_OUT2-2") (pin "2") (pinfunction "2_2") (pintype "passive"))
      (node (ref "IC10") (pin "GND") (pinfunction "GND_GND") (pintype "power_in"))
      (node (ref "IC10") (pin "GND6") (pinfunction "GND_GND6") (pintype "power_in"))
      (node (ref "IC11") (pin "GND") (pinfunction "GND_GND") (pintype "bidirectional"))
      (node (ref "IC12") (pin "S2") (pinfunction "S2_S2") (pintype "bidirectional"))
      (node (ref "IC14") (pin "GND") (pinfunction "GND_GND") (pintype "power_in"))
      (node (ref "IC14") (pin "VSS") (pinfunction "GND_VSS") (pintype "power_in"))
      (node (ref "IC15") (pin "3") (pinfunction "GND_3") (pintype "bidirectional"))
      (node (ref "IC16") (pin "4S") (pinfunction "S_4S") (pintype "passive"))
      (node (ref "IC16") (pin "S") (pinfunction "S_S") (pintype "passive"))
      (node (ref "IC17") (pin "ANODE") (pinfunction "ANODE_ANODE") (pintype "bidirectional"))
      (node (ref "IC3") (pin "11SGND") (pinfunction "SGND_11SGND") (pintype "bidirectional"))
      (node (ref "IC3") (pin "GND10") (pinfunction "PGND_GND10") (pintype "bidirectional"))
      (node (ref "IC3") (pin "GND2") (pinfunction "PGND_GND2") (pintype "bidirectional"))
      (node (ref "IC3") (pin "GND3") (pinfunction "PGND_GND3") (pintype "bidirectional"))
      (node (ref "IC3") (pin "GND4") (pinfunction "PGND_GND4") (pintype "bidirectional"))
      (node (ref "IC3") (pin "GND5") (pinfunction "PGND_GND5") (pintype "bidirectional"))
      (node (ref "IC3") (pin "GND6") (pinfunction "PGND_GND6") (pintype "bidirectional"))
      (node (ref "IC3") (pin "GND7") (pinfunction "PGND_GND7") (pintype "bidirectional"))
      (node (ref "IC3") (pin "GND8") (pinfunction "PGND_GND8") (pintype "bidirectional"))
      (node (ref "IC3") (pin "GND9") (pinfunction "PGND_GND9") (pintype "bidirectional"))
      (node (ref "IC3") (pin "PGND") (pinfunction "PGND_PGND") (pintype "bidirectional"))
      (node (ref "IC6") (pin "ANODE") (pinfunction "ANODE_ANODE") (pintype "bidirectional"))
      (node (ref "IC7") (pin "8") (pinfunction "GND_8") (pintype "bidirectional"))
      (node (ref "IC7") (pin "GND") (pinfunction "GND_GND") (pintype "bidirectional"))
      (node (ref "IC9") (pin "S1") (pinfunction "S1_S1") (pintype "bidirectional"))
      (node (ref "JP6") (pin "2") (pinfunction "2_2") (pintype "passive"))
      (node (ref "MN3") (pin "4S") (pinfunction "S_4S") (pintype "passive"))
      (node (ref "MN3") (pin "S") (pinfunction "S_S") (pintype "passive"))
      (node (ref "R13") (pin "2") (pinfunction "2_2") (pintype "passive"))
      (node (ref "R_CAPRTN") (pin "2") (pinfunction "2_2") (pintype "passive"))
      (node (ref "R_FB02") (pin "2") (pinfunction "2_2") (pintype "passive"))
      (node (ref "R_FBC2") (pin "1") (pinfunction "1_1") (pintype "passive"))
      (node (ref "R_PF3") (pin "2") (pinfunction "2_2") (pintype "passive"))
      (node (ref "R_T") (pin "2") (pinfunction "2_2") (pintype "passive"))
      (node (ref "R_T1") (pin "2") (pinfunction "2_2") (pintype "passive"))
      (node (ref "R_TST") (pin "2") (pinfunction "2_2") (pintype "passive"))
      (node (ref "X2") (pin "1") (pinfunction "S_1") (pintype "passive"))
    )
    (net (code "27") (name "/GPI") (class "Default")
      (node (ref "IC3") (pin "13-GPI") (pinfunction "GPI_13-GPI") (pintype "bidirectional"))
      (node (ref "R1") (pin "2") (pinfunction "2_2") (pintype "passive"))
      (node (ref "R_T1") (pin "1") (pinfunction "1_1") (pintype "passive"))
    )
    (net (code "28") (name "/I2C_SDA") (class "Default")
      (node (ref "IC15") (pin "2") (pinfunction "COM_2") (pintype "bidirectional"))
      (node (ref "IC3") (pin "5-SDA") (pinfunction "SDA_5-SDA") (pintype "bidirectional"))
    )
    (net (code "29") (name "/ICAP") (class "Default")
      (node (ref "IC3") (pin "25-ICAP") (pinfunction "ICAP_25-ICAP") (pintype "bidirectional"))
      (node (ref "L1") (pin "2") (pinfunction "2_2") (pintype "passive"))
      (node (ref "R_SNSC") (pin "1") (pinfunction "1_1") (pintype "passive"))
    )
    (net (code "30") (name "/ICSP_DI{slash}MISO") (class "Default")
      (node (ref "CONN1") (pin "2") (pinfunction "2_2") (pintype "bidirectional"))
      (node (ref "IC15") (pin "1") (pinfunction "NO_1") (pintype "bidirectional"))
      (node (ref "IC7") (pin "15") (pinfunction "MOSI/DI/SDA/PCINT5-PB5_15") (pintype "bidirectional"))
      (node (ref "R24") (pin "6") (pinfunction "6_6") (pintype "bidirectional"))
    )
    (net (code "31") (name "/ICSP_DO{slash}MOSI") (class "Default")
      (node (ref "CONN1") (pin "3") (pinfunction "3_3") (pintype "bidirectional"))
      (node (ref "IC7") (pin "16") (pinfunction "MISO/DO/PCINT6-PB6_16") (pintype "bidirectional"))
      (node (ref "R24") (pin "4") (pinfunction "4_4") (pintype "bidirectional"))
    )
    (net (code "32") (name "/ICSP_SCK") (class "Default")
      (node (ref "CONN1") (pin "4") (pinfunction "4_4") (pintype "bidirectional"))
      (node (ref "IC3") (pin "4-SCL") (pinfunction "SCL_4-SCL") (pintype "bidirectional"))
      (node (ref "IC7") (pin "17") (pinfunction "USCK/SCL/SCK/PCINT7-PB7_17") (pintype "bidirectional"))
      (node (ref "R24") (pin "2") (pinfunction "2_2") (pintype "bidirectional"))
    )
    (net (code "33") (name "/INT1") (class "Default")
      (node (ref "IC10") (pin "!INT!") (pinfunction "~{INT}_!INT!") (pintype "bidirectional"))
      (node (ref "IC7") (pin "5") (pinfunction "PCINT14/INT1-PD3_5") (pintype "bidirectional"))
    )
    (net (code "34") (name "/ITST") (class "Default")
      (node (ref "IC3") (pin "14-ITST") (pinfunction "ITST_14-ITST") (pintype "bidirectional"))
      (node (ref "R_TST") (pin "1") (pinfunction "1_1") (pintype "passive"))
    )
    (net (code "35") (name "/OUT+") (class "Default")
      (node (ref "C31") (pin "+") (pinfunction "+_+") (pintype "passive"))
      (node (ref "IC12") (pin "D1") (pinfunction "D1_D1") (pintype "bidirectional"))
      (node (ref "IC13") (pin "CATHODE") (pinfunction "CATHODE_CATHODE") (pintype "bidirectional"))
      (node (ref "IC8") (pin "CATHODE") (pinfunction "CATHODE_CATHODE") (pintype "bidirectional"))
      (node (ref "IC9") (pin "D2") (pinfunction "D2_D2") (pintype "bidirectional"))
      (node (ref "JP4") (pin "1") (pinfunction "1_1") (pintype "passive"))
    )
    (net (code "36") (name "/OUTFB") (class "Default")
      (node (ref "C5") (pin "2") (pinfunction "2_2") (pintype "passive"))
      (node (ref "IC3") (pin "10-OUTFB") (pinfunction "OUTFB_10-OUTFB") (pintype "bidirectional"))
      (node (ref "R_FB01") (pin "2") (pinfunction "2_2") (pintype "passive"))
      (node (ref "R_FB02") (pin "1") (pinfunction "1_1") (pintype "passive"))
    )
    (net (code "37") (name "/OV") (class "Default")
      (node (ref "IC3") (pin "43-OV") (pinfunction "OV_43-OV") (pintype "bidirectional"))
      (node (ref "R_PF2") (pin "2") (pinfunction "2_2") (pintype "passive"))
      (node (ref "R_PF3") (pin "1") (pinfunction "1_1") (pintype "passive"))
    )
    (net (code "38") (name "/RESET") (class "Default")
      (node (ref "IC10") (pin "!RESET!") (pinfunction "~{RESET}_!RESET!") (pintype "bidirectional"))
      (node (ref "R23") (pin "4") (pinfunction "4_4") (pintype "bidirectional"))
    )
    (net (code "39") (name "/RETRYB") (class "Default")
      (node (ref "IC3") (pin "34-RETRYB") (pinfunction "RETRYB_34-RETRYB") (pintype "bidirectional"))
      (node (ref "R13") (pin "1") (pinfunction "1_1") (pintype "passive"))
      (node (ref "R14") (pin "1") (pinfunction "1_1") (pintype "passive"))
    )
    (net (code "40") (name "/RT") (class "Default")
      (node (ref "IC3") (pin "12-RT") (pinfunction "RT_12-RT") (pintype "bidirectional"))
      (node (ref "R_T") (pin "1") (pinfunction "1_1") (pintype "passive"))
    )
    (net (code "41") (name "/RXCAN") (class "Default")
      (node (ref "IC10") (pin "RXCAN") (pinfunction "RXCAN_RXCAN") (pintype "input"))
      (node (ref "IC14") (pin "RXD") (pinfunction "RXD_RXD") (pintype "output"))
    )
    (net (code "42") (name "/SPI_MISO") (class "Default")
      (node (ref "IC10") (pin "SO") (pinfunction "SO_SO") (pintype "output"))
      (node (ref "R24") (pin "5") (pinfunction "5_5") (pintype "bidirectional"))
    )
    (net (code "43") (name "/SPI_MOSI") (class "Default")
      (node (ref "IC10") (pin "SI") (pinfunction "SI_SI") (pintype "input"))
      (node (ref "R24") (pin "3") (pinfunction "3_3") (pintype "bidirectional"))
    )
    (net (code "44") (name "/SPI_SCK") (class "Default")
      (node (ref "IC10") (pin "SCK") (pinfunction "SCK_SCK") (pintype "bidirectional"))
      (node (ref "R24") (pin "1") (pinfunction "1_1") (pintype "bidirectional"))
    )
    (net (code "45") (name "/SPI_SS") (class "Default")
      (node (ref "IC10") (pin "!CS!") (pinfunction "~{CS}_!CS!") (pintype "bidirectional"))
      (node (ref "IC15") (pin "4") (pinfunction "IN_4") (pintype "bidirectional"))
      (node (ref "IC7") (pin "14") (pinfunction "OC1B/PCINT4-PB4_14") (pintype "bidirectional"))
      (node (ref "R24") (pin "8") (pinfunction "8_8") (pintype "bidirectional"))
    )
    (net (code "46") (name "/STBY") (class "Default")
      (node (ref "IC14") (pin "STBY") (pinfunction "STBY_STBY") (pintype "bidirectional"))
      (node (ref "IC7") (pin "11") (pinfunction "AIN1/PCINT1-PB1_11") (pintype "bidirectional"))
      (node (ref "R23") (pin "2") (pinfunction "2_2") (pintype "bidirectional"))
    )
    (net (code "47") (name "/SW") (class "Default")
      (node (ref "C6") (pin "2") (pinfunction "2_2") (pintype "passive"))
      (node (ref "IC3") (pin "27-SW") (pinfunction "SW_27-SW") (pintype "bidirectional"))
      (node (ref "L1") (pin "1") (pinfunction "1_1") (pintype "passive"))
      (node (ref "MN2") (pin "4S") (pinfunction "S_4S") (pintype "passive"))
      (node (ref "MN2") (pin "S") (pinfunction "S_S") (pintype "passive"))
      (node (ref "MN3") (pin "1D") (pinfunction "D_1D") (pintype "passive"))
      (node (ref "MN3") (pin "2D") (pinfunction "D_2D") (pintype "passive"))
      (node (ref "MN3") (pin "5D") (pinfunction "D_5D") (pintype "passive"))
      (node (ref "MN3") (pin "6D") (pinfunction "D_6D") (pintype "passive"))
      (node (ref "MN3") (pin "D") (pinfunction "D_D") (pintype "passive"))
    )
    (net (code "48") (name "/TGATE") (class "Default")
      (node (ref "IC3") (pin "28-TGATE") (pinfunction "TGATE_28-TGATE") (pintype "bidirectional"))
      (node (ref "MN2") (pin "3G") (pinfunction "G_3G") (pintype "passive"))
    )
    (net (code "49") (name "/TXCAN") (class "Default")
      (node (ref "IC10") (pin "TXCAN") (pinfunction "TXCAN_TXCAN") (pintype "output"))
      (node (ref "IC14") (pin "TXD") (pinfunction "TXD_TXD") (pintype "input"))
    )
    (net (code "50") (name "/UV") (class "Default")
      (node (ref "IC3") (pin "42-UV") (pinfunction "UV_42-UV") (pintype "bidirectional"))
      (node (ref "R_PF1") (pin "2") (pinfunction "2_2") (pintype "passive"))
      (node (ref "R_PF2") (pin "1") (pinfunction "1_1") (pintype "passive"))
    )
    (net (code "51") (name "/VC") (class "Default")
      (node (ref "IC3") (pin "8-VC") (pinfunction "VC_8-VC") (pintype "bidirectional"))
      (node (ref "R2") (pin "1") (pinfunction "1_1") (pintype "passive"))
    )
    (net (code "52") (name "/VCAP") (class "Default")
      (node (ref "CAP4") (pin "+") (pinfunction "+_+") (pintype "passive"))
      (node (ref "C_CAP1") (pin "1") (pinfunction "1_1") (pintype "passive"))
      (node (ref "C_CAP2") (pin "1") (pinfunction "1_1") (pintype "passive"))
      (node (ref "C_CAP3") (pin "1") (pinfunction "1_1") (pintype "passive"))
      (node (ref "C_CAP4") (pin "1") (pinfunction "1_1") (pintype "passive"))
      (node (ref "C_CP5") (pin "1") (pinfunction "1_1") (pintype "passive"))
      (node (ref "IC3") (pin "24-VCAP") (pinfunction "VCAP_24-VCAP") (pintype "bidirectional"))
      (node (ref "R_CAP4") (pin "2") (pinfunction "2_2") (pintype "passive"))
      (node (ref "R_FBC1") (pin "2") (pinfunction "2_2") (pintype "passive"))
      (node (ref "R_SNSC") (pin "2") (pinfunction "2_2") (pintype "passive"))
    )
    (net (code "53") (name "/VCAPP5") (class "Default")
      (node (ref "C_CP5") (pin "2") (pinfunction "2_2") (pintype "passive"))
      (node (ref "IC3") (pin "22-VCAPP5") (pinfunction "VCAPP5_22-VCAPP5") (pintype "bidirectional"))
    )
    (net (code "54") (name "/VCC2P5") (class "Default")
      (node (ref "C1") (pin "1") (pinfunction "1_1") (pintype "passive"))
      (node (ref "IC3") (pin "1-CAP_SLCT0") (pinfunction "CAP_SLCT0_1-CAP_SLCT0") (pintype "bidirectional"))
      (node (ref "IC3") (pin "2-CAP_SLCT1") (pinfunction "CAP_SLCT1_2-CAP_SLCT1") (pintype "bidirectional"))
      (node (ref "IC3") (pin "26-VCC2P5") (pinfunction "VCC2P5_26-VCC2P5") (pintype "bidirectional"))
      (node (ref "R1") (pin "1") (pinfunction "1_1") (pintype "passive"))
    )
    (net (code "55") (name "/VDD") (class "Default")
      (node (ref "R3") (pin "1") (pinfunction "1_1") (pintype "passive"))
      (node (ref "R4") (pin "1") (pinfunction "1_1") (pintype "passive"))
      (node (ref "R8") (pin "1") (pinfunction "1_1") (pintype "passive"))
    )
    (net (code "56") (name "/VIN") (class "Default")
      (node (ref "JP1") (pin "2") (pinfunction "2_2") (pintype "passive"))
      (node (ref "MN1") (pin "1D") (pinfunction "D_1D") (pintype "passive"))
      (node (ref "MN1") (pin "2D") (pinfunction "D_2D") (pintype "passive"))
      (node (ref "MN1") (pin "5D") (pinfunction "D_5D") (pintype "passive"))
      (node (ref "MN1") (pin "6D") (pinfunction "D_6D") (pintype "passive"))
      (node (ref "MN1") (pin "D") (pinfunction "D_D") (pintype "passive"))
      (node (ref "R9") (pin "2") (pinfunction "2_2") (pintype "passive"))
      (node (ref "R_PF1") (pin "1") (pinfunction "1_1") (pintype "passive"))
    )
    (net (code "57") (name "/XTAL1") (class "Default")
      (node (ref "IC11") (pin "XTAL1") (pinfunction "XTAL1_XTAL1") (pintype "bidirectional"))
      (node (ref "IC7") (pin "3") (pinfunction "PCINT8/CLKI/XTAL1-PA0_3") (pintype "bidirectional"))
    )
    (net (code "58") (name "/XTAL2") (class "Default")
      (node (ref "IC11") (pin "XTAL2") (pinfunction "XTAL2_XTAL2") (pintype "bidirectional"))
      (node (ref "IC7") (pin "2") (pinfunction "PCINT9/XTAL2-PA1_2") (pintype "bidirectional"))
    )
    (net (code "59") (name "/ZERO_CROSS") (class "Default")
      (node (ref "IC16") (pin "1D") (pinfunction "D_1D") (pintype "passive"))
      (node (ref "IC16") (pin "2D") (pinfunction "D_2D") (pintype "passive"))
      (node (ref "IC16") (pin "5D") (pinfunction "D_5D") (pintype "passive"))
      (node (ref "IC16") (pin "6D") (pinfunction "D_6D") (pintype "passive"))
      (node (ref "IC16") (pin "D") (pinfunction "D_D") (pintype "passive"))
      (node (ref "JP8") (pin "1") (pinfunction "1_1") (pintype "passive"))
      (node (ref "R25") (pin "1") (pinfunction "1_1") (pintype "passive"))
    )
    (net (code "60") (name "/~{PFO}") (class "Default")
      (node (ref "IC3") (pin "3-VINGD") (pinfunction "VINGD_3-VINGD") (pintype "output"))
      (node (ref "R8") (pin "2") (pinfunction "2_2") (pintype "passive"))
    )
    (net (code "61") (name "/~{SMBALERT}") (class "Default")
      (node (ref "IC3") (pin "6-!SMBALERT!") (pinfunction "~{SMBALERT}_6-!SMBALERT!") (pintype "output"))
      (node (ref "IC7") (pin "12") (pinfunction "OC0A/PCINT2-PB2_12") (pintype "bidirectional"))
      (node (ref "R3") (pin "2") (pinfunction "2_2") (pintype "passive"))
    )
    (net (code "62") (name "Net-(C27-Pad1)") (class "Default")
      (node (ref "C27") (pin "1") (pinfunction "1_1") (pintype "passive"))
      (node (ref "IC6") (pin "VCAPL") (pinfunction "VCAPL_VCAPL") (pintype "bidirectional"))
    )
    (net (code "63") (name "Net-(C27-Pad2)") (class "Default")
      (node (ref "C27") (pin "2") (pinfunction "2_2") (pintype "passive"))
      (node (ref "IC6") (pin "VCAPH") (pinfunction "VCAPH_VCAPH") (pintype "bidirectional"))
    )
    (net (code "64") (name "Net-(C30-Pad1)") (class "Default")
      (node (ref "C30") (pin "1") (pinfunction "1_1") (pintype "passive"))
      (node (ref "IC8") (pin "VCAPL") (pinfunction "VCAPL_VCAPL") (pintype "bidirectional"))
    )
    (net (code "65") (name "Net-(C30-Pad2)") (class "Default")
      (node (ref "C30") (pin "2") (pinfunction "2_2") (pintype "passive"))
      (node (ref "IC8") (pin "VCAPH") (pinfunction "VCAPH_VCAPH") (pintype "bidirectional"))
    )
    (net (code "66") (name "Net-(C33-Pad1)") (class "Default")
      (node (ref "C33") (pin "1") (pinfunction "1_1") (pintype "passive"))
      (node (ref "IC13") (pin "VCAPL") (pinfunction "VCAPL_VCAPL") (pintype "bidirectional"))
    )
    (net (code "67") (name "Net-(C33-Pad2)") (class "Default")
      (node (ref "C33") (pin "2") (pinfunction "2_2") (pintype "passive"))
      (node (ref "IC13") (pin "VCAPH") (pinfunction "VCAPH_VCAPH") (pintype "bidirectional"))
    )
    (net (code "68") (name "Net-(C34-Pad1)") (class "Default")
      (node (ref "C34") (pin "1") (pinfunction "1_1") (pintype "passive"))
      (node (ref "IC17") (pin "VCAPL") (pinfunction "VCAPL_VCAPL") (pintype "bidirectional"))
    )
    (net (code "69") (name "Net-(C34-Pad2)") (class "Default")
      (node (ref "C34") (pin "2") (pinfunction "2_2") (pintype "passive"))
      (node (ref "IC17") (pin "VCAPH") (pinfunction "VCAPH_VCAPH") (pintype "bidirectional"))
    )
    (net (code "70") (name "Net-(CAP1-Pad+)") (class "Default")
      (node (ref "CAP1") (pin "+") (pinfunction "+_+") (pintype "passive"))
      (node (ref "CAP2") (pin "-") (pinfunction "-_-") (pintype "passive"))
      (node (ref "R_CAP1") (pin "2") (pinfunction "2_2") (pintype "passive"))
    )
    (net (code "71") (name "Net-(CAP2-Pad+)") (class "Default")
      (node (ref "CAP2") (pin "+") (pinfunction "+_+") (pintype "passive"))
      (node (ref "CAP3") (pin "-") (pinfunction "-_-") (pintype "passive"))
      (node (ref "R_CAP2") (pin "2") (pinfunction "2_2") (pintype "passive"))
    )
    (net (code "72") (name "Net-(CAP3-Pad+)") (class "Default")
      (node (ref "CAP3") (pin "+") (pinfunction "+_+") (pintype "passive"))
      (node (ref "CAP4") (pin "-") (pinfunction "-_-") (pintype "passive"))
      (node (ref "R_CAP3") (pin "2") (pinfunction "2_2") (pintype "passive"))
    )
    (net (code "73") (name "Net-(C_C-Pad1)") (class "Default")
      (node (ref "C_C") (pin "1") (pinfunction "1_1") (pintype "passive"))
      (node (ref "R2") (pin "2") (pinfunction "2_2") (pintype "passive"))
    )
    (net (code "74") (name "Net-(D2-PadCAT)") (class "Default")
      (node (ref "D2") (pin "CAT") (pinfunction "CAT_CAT") (pintype "passive"))
      (node (ref "D3") (pin "CAT") (pinfunction "CAT_CAT") (pintype "passive"))
    )
    (net (code "75") (name "Net-(IC3-CTIMER)") (class "Default")
      (node (ref "C3") (pin "2") (pinfunction "2_2") (pintype "passive"))
      (node (ref "IC3") (pin "44-CTIMER") (pinfunction "CTIMER_44-CTIMER") (pintype "bidirectional"))
    )
    (net (code "76") (name "Net-(IC3-HS_GATE)") (class "Default")
      (node (ref "IC3") (pin "40-HS_GATE") (pinfunction "HS_GATE_40-HS_GATE") (pintype "bidirectional"))
      (node (ref "R10") (pin "2") (pinfunction "2_2") (pintype "passive"))
      (node (ref "R11") (pin "1") (pinfunction "1_1") (pintype "passive"))
    )
    (net (code "77") (name "Net-(IC3-ISNSP_CHG)") (class "Default")
      (node (ref "IC3") (pin "36-ISNSP_CHG") (pinfunction "ISNSP_CHG_36-ISNSP_CHG") (pintype "bidirectional"))
      (node (ref "IC3") (pin "37-ISNS_HS") (pinfunction "ISNSP_HS_37-ISNS_HS") (pintype "bidirectional"))
      (node (ref "MN5") (pin "1D") (pinfunction "D_1D") (pintype "passive"))
      (node (ref "MN5") (pin "2D") (pinfunction "D_2D") (pintype "passive"))
      (node (ref "MN5") (pin "5D") (pinfunction "D_5D") (pintype "passive"))
      (node (ref "MN5") (pin "6D") (pinfunction "D_6D") (pintype "passive"))
      (node (ref "MN5") (pin "D") (pinfunction "D_D") (pintype "passive"))
      (node (ref "R_SNSI") (pin "1") (pinfunction "1_1") (pintype "passive"))
    )
    (net (code "78") (name "Net-(IC3-SRC)") (class "Default")
      (node (ref "IC3") (pin "39_SRC") (pinfunction "SRC_39_SRC") (pintype "power_in"))
      (node (ref "MN1") (pin "4S") (pinfunction "S_4S") (pintype "passive"))
      (node (ref "MN1") (pin "S") (pinfunction "S_S") (pintype "passive"))
      (node (ref "MN5") (pin "4S") (pinfunction "S_4S") (pintype "passive"))
      (node (ref "MN5") (pin "S") (pinfunction "S_S") (pintype "passive"))
    )
    (net (code "79") (name "Net-(IC3-VIN)") (class "Default")
      (node (ref "IC3") (pin "41-VIN") (pinfunction "VIN_41-VIN") (pintype "bidirectional"))
      (node (ref "R9") (pin "1") (pinfunction "1_1") (pintype "passive"))
    )
    (net (code "80") (name "Net-(JP1-Pad1)") (class "Default")
      (node (ref "JP1") (pin "1") (pinfunction "1_1") (pintype "passive"))
      (node (ref "JP4") (pin "2") (pinfunction "2_2") (pintype "passive"))
      (node (ref "JP6") (pin "1") (pinfunction "1_1") (pintype "passive"))
    )
    (net (code "81") (name "Net-(MN1-G)") (class "Default")
      (node (ref "MN1") (pin "3G") (pinfunction "G_3G") (pintype "passive"))
      (node (ref "R10") (pin "1") (pinfunction "1_1") (pintype "passive"))
    )
    (net (code "82") (name "Net-(MN5-G)") (class "Default")
      (node (ref "MN5") (pin "3G") (pinfunction "G_3G") (pintype "passive"))
      (node (ref "R11") (pin "2") (pinfunction "2_2") (pintype "passive"))
    )
    (net (code "83") (name "unconnected-(IC3-OUTFET-Pad23-OUTFET)") (class "Default")
      (node (ref "IC3") (pin "23-OUTFET") (pinfunction "OUTFET_23-OUTFET") (pintype "bidirectional"))
    )
    (net (code "84") (name "unconnected-(IC7-AIN0{slash}PCINT0-PB0-Pad10)") (class "Default")
      (node (ref "IC7") (pin "10") (pinfunction "AIN0/PCINT0-PB0_10") (pintype "bidirectional"))
    )
    (net (code "85") (name "unconnected-(IC7-OC1A{slash}PCINT3-PB3-Pad13)") (class "Default")
      (node (ref "IC7") (pin "13") (pinfunction "OC1A/PCINT3-PB3_13") (pintype "bidirectional"))
    )
    (net (code "86") (name "unconnected-(IC7-PCINT12{slash}TXD-PD1-Pad1)") (class "Default")
      (node (ref "IC7") (pin "1") (pinfunction "PCINT12/TXD-PD1_1") (pintype "bidirectional"))
    )
    (net (code "87") (name "unconnected-(IC7-PCINT15{slash}T0-PD4-Pad6)") (class "Default")
      (node (ref "IC7") (pin "6") (pinfunction "PCINT15/T0-PD4_6") (pintype "bidirectional"))
    )
    (net (code "88") (name "unconnected-(IC7-PCINT16{slash}OC0B{slash}T1-PD5-Pad7)") (class "Default")
      (node (ref "IC7") (pin "7") (pinfunction "PCINT16/OC0B/T1-PD5_7") (pintype "bidirectional"))
    )
    (net (code "89") (name "unconnected-(IC7-PCINT17{slash}ICPI-PD6-Pad9)") (class "Default")
      (node (ref "IC7") (pin "9") (pinfunction "PCINT17/ICPI-PD6_9") (pintype "bidirectional"))
    )
    (net (code "90") (name "unconnected-(IC7-RXD{slash}PCINT11-PD0-Pad20)") (class "Default")
      (node (ref "IC7") (pin "20") (pinfunction "RXD/PCINT11-PD0_20") (pintype "bidirectional"))
    )
    (net (code "91") (name "unconnected-(IC10-NC-PadNC1)") (class "Default")
      (node (ref "IC10") (pin "NC1") (pinfunction "NC_NC1") (pintype "no_connect"))
    )
    (net (code "92") (name "unconnected-(IC10-NC-PadNC2)") (class "Default")
      (node (ref "IC10") (pin "NC2") (pinfunction "NC_NC2") (pintype "no_connect"))
    )
    (net (code "93") (name "unconnected-(IC10-PadCLKOUT)") (class "Default")
      (node (ref "IC10") (pin "CLKOUT") (pinfunction "CLKOUT_CLKOUT") (pintype "bidirectional"))
    )
    (net (code "94") (name "unconnected-(IC10-PadOSC2)") (class "Default")
      (node (ref "IC10") (pin "OSC2") (pinfunction "OSC2_OSC2") (pintype "bidirectional"))
    )
    (net (code "95") (name "unconnected-(IC10-~{RX0BF}-Pad!RX0BF!)") (class "Default")
      (node (ref "IC10") (pin "!RX0BF!") (pinfunction "~{RX0BF}_!RX0BF!") (pintype "bidirectional"))
    )
    (net (code "96") (name "unconnected-(IC10-~{RX1BF}-Pad!RX1BF!)") (class "Default")
      (node (ref "IC10") (pin "!RX1BF!") (pinfunction "~{RX1BF}_!RX1BF!") (pintype "bidirectional"))
    )
    (net (code "97") (name "unconnected-(IC10-~{TX0RTS}-Pad!TX0RTS!)") (class "Default")
      (node (ref "IC10") (pin "!TX0RTS!") (pinfunction "~{TX0RTS}_!TX0RTS!") (pintype "bidirectional"))
    )
    (net (code "98") (name "unconnected-(IC10-~{TX1RTS}-Pad!TX1RTS!)") (class "Default")
      (node (ref "IC10") (pin "!TX1RTS!") (pinfunction "~{TX1RTS}_!TX1RTS!") (pintype "bidirectional"))
    )
    (net (code "99") (name "unconnected-(IC10-~{TX2RTS}-Pad!TX2RTS!)") (class "Default")
      (node (ref "IC10") (pin "!TX2RTS!") (pinfunction "~{TX2RTS}_!TX2RTS!") (pintype "bidirectional"))
    )
    (net (code "100") (name "unconnected-(IC14-PadSPLIT)") (class "Default")
      (node (ref "IC14") (pin "SPLIT") (pinfunction "SPLIT_SPLIT") (pintype "bidirectional"))
    )
    (net (code "101") (name "unconnected-(R23-Pad5)") (class "Default")
      (node (ref "R23") (pin "5") (pinfunction "5_5") (pintype "bidirectional"))
    )
    (net (code "102") (name "unconnected-(R23-Pad6)") (class "Default")
      (node (ref "R23") (pin "6") (pinfunction "6_6") (pintype "bidirectional"))
    )
    (net (code "103") (name "unconnected-(R23-Pad7)") (class "Default")
      (node (ref "R23") (pin "7") (pinfunction "7_7") (pintype "bidirectional"))
    )
    (net (code "104") (name "unconnected-(R23-Pad8)") (class "Default")
      (node (ref "R23") (pin "8") (pinfunction "8_8") (pintype "bidirectional"))
    )
  )
)
